# blueduino-r2.net
KiCad netlist of a schematic drawn in Altium Designer
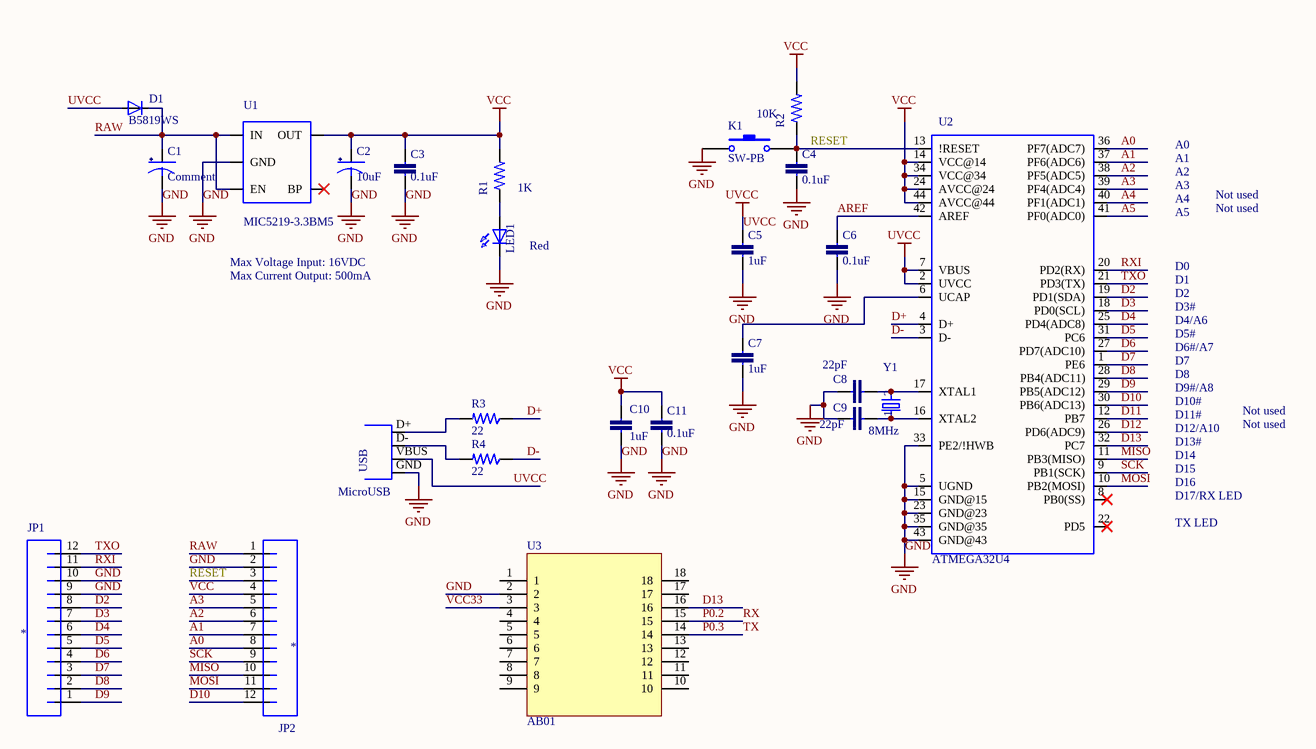
[diagram p0: blueduino-r2.SchDoc]

(export (version "E")
  (design (tool "Eeschema 10.0.6"))
  (components
    (comp (ref "C1") (value "Comment") (footprint "0603C") (libsource (lib "SparkFun") (part "CAP_POL1206")))
    (comp (ref "C2") (value "10uF") (footprint "EIA3216") (libsource (lib "SparkFun") (part "CAP_POL1206")))
    (comp (ref "C3") (value "0.1uF") (footprint "0402-CAP") (libsource (lib "SparkFun") (part "CAP0402-CAP")))
    (comp (ref "C4") (value "0.1uF") (footprint "0402-CAP") (libsource (lib "SparkFun") (part "CAP0402-CAP")))
    (comp (ref "C5") (value "1uF") (footprint "0402-CAP") (libsource (lib "SparkFun") (part "CAP0402-CAP")))
    (comp (ref "C6") (value "0.1uF") (footprint "0402-CAP") (libsource (lib "SparkFun") (part "CAP0402-CAP")))
    (comp (ref "C7") (value "1uF") (footprint "0402-CAP") (libsource (lib "SparkFun") (part "CAP0402-CAP")))
    (comp (ref "C8") (value "22pF") (footprint "0402-CAP") (libsource (lib "") (part "CAP0402-CAP_1")))
    (comp (ref "C9") (value "22pF") (footprint "0402-CAP") (libsource (lib "") (part "CAP0402-CAP_1")))
    (comp (ref "C10") (value "1uF") (footprint "0402-CAP") (libsource (lib "") (part "CAP0402-CAP_2")))
    (comp (ref "C11")
      (value "0.1uF")
      (footprint "0402-CAP")
      (libsource (lib "SparkFun") (part "CAP0402-CAP"))
    )
    (comp (ref "D1") (value "B5819WS") (footprint "SOD-323") (libsource (lib "SparkFun") (part "DIODESOD")))
    (comp (ref "JP1") (value "*") (footprint "1X12") (libsource (lib "SparkFun") (part "M12PTH")))
    (comp (ref "JP2") (value "*") (footprint "1X12") (libsource (lib "SparkFun") (part "M12PTH")))
    (comp (ref "K1")
      (value "SW-PB")
      (footprint "SPST-2")
      (description "Switch")
      (fields (field (name "PUBLISHER") "Altium Limited"))
      (libsource (lib "Miscellaneous Devices") (part "SW-PB"))
    )
    (comp (ref "LED1") (value "Red") (footprint "LED-0603") (libsource (lib "SparkFun") (part "LED0603")))
    (comp (ref "R1")
      (value "1K")
      (footprint "0402-RES")
      (libsource (lib "SparkFun") (part "RESISTOR0402-RES"))
    )
    (comp (ref "R2")
      (value "10K")
      (footprint "0402-RES")
      (libsource (lib "SparkFun") (part "RESISTOR0402-RES"))
    )
    (comp (ref "R3") (value "22") (footprint "0402-RES") (libsource (lib "") (part "RESISTOR0402-RES_1")))
    (comp (ref "R4") (value "22") (footprint "0402-RES") (libsource (lib "") (part "RESISTOR0402-RES_1")))
    (comp (ref "U1")
      (value "MIC5219-3.3BM5")
      (footprint "SOT23-5")
      (libsource (lib "SparkFun") (part "V_REG_LDOSMD"))
    )
    (comp (ref "U2")
      (value "ATMEGA32U4")
      (footprint "QFN-44-NOPAD")
      (libsource (lib "SparkFun") (part "ATMEGA32U4QFN2"))
    )
    (comp (ref "U3")
      (value "AB01")
      (footprint "CC2540-MINI")
      (description "Header, 25-Pin")
      (fields (field (name "PUBLISHER") "Altium Limited"))
      (libsource (lib "myschlib") (part "CC2541_S02"))
    )
    (comp (ref "X1")
      (value "MicroUSB")
      (footprint "USB-MICROB")
      (libsource (lib "SparkFun") (part "USB-MICROB"))
    )
    (comp (ref "Y1")
      (value "8MHz")
      (footprint "OSCCC250X320X80-4L")
      (libsource (lib "SparkFun") (part "CRYSTAL5X3"))
    )
  )
  (nets
    (net (code "1") (name "/A0") (class "Default")
      (node (ref "JP2") (pin "8") (pinfunction "8_8") (pintype "passive"))
      (node (ref "U2") (pin "36") (pinfunction "PF7(ADC7)_36") (pintype "passive"))
    )
    (net (code "2") (name "/A1") (class "Default")
      (node (ref "JP2") (pin "7") (pinfunction "7_7") (pintype "passive"))
      (node (ref "U2") (pin "37") (pinfunction "PF6(ADC6)_37") (pintype "passive"))
    )
    (net (code "3") (name "/A2") (class "Default")
      (node (ref "JP2") (pin "6") (pinfunction "6_6") (pintype "passive"))
      (node (ref "U2") (pin "38") (pinfunction "PF5(ADC5)_38") (pintype "passive"))
    )
    (net (code "4") (name "/A3") (class "Default")
      (node (ref "JP2") (pin "5") (pinfunction "5_5") (pintype "passive"))
      (node (ref "U2") (pin "39") (pinfunction "PF4(ADC4)_39") (pintype "passive"))
    )
    (net (code "5") (name "/A4") (class "Default")
      (node (ref "U2") (pin "40") (pinfunction "PF1(ADC1)_40") (pintype "passive"))
    )
    (net (code "6") (name "/A5") (class "Default")
      (node (ref "U2") (pin "41") (pinfunction "PF0(ADC0)_41") (pintype "passive"))
    )
    (net (code "7") (name "/AREF") (class "Default")
      (node (ref "C6") (pin "2") (pinfunction "2_2") (pintype "passive"))
      (node (ref "U2") (pin "42") (pinfunction "AREF_42") (pintype "passive"))
    )
    (net (code "8") (name "/D+") (class "Default")
      (node (ref "R3") (pin "1") (pinfunction "1_1") (pintype "passive"))
      (node (ref "U2") (pin "4") (pinfunction "D+_4") (pintype "passive"))
    )
    (net (code "9") (name "/D-") (class "Default")
      (node (ref "R4") (pin "1") (pinfunction "1_1") (pintype "passive"))
      (node (ref "U2") (pin "3") (pinfunction "D-_3") (pintype "passive"))
    )
    (net (code "10") (name "/D2") (class "Default")
      (node (ref "JP1") (pin "8") (pinfunction "8_8") (pintype "passive"))
      (node (ref "U2") (pin "19") (pinfunction "PD1(SDA)_19") (pintype "passive"))
    )
    (net (code "11") (name "/D3") (class "Default")
      (node (ref "JP1") (pin "7") (pinfunction "7_7") (pintype "passive"))
      (node (ref "U2") (pin "18") (pinfunction "PD0(SCL)_18") (pintype "passive"))
    )
    (net (code "12") (name "/D4") (class "Default")
      (node (ref "JP1") (pin "6") (pinfunction "6_6") (pintype "passive"))
      (node (ref "U2") (pin "25") (pinfunction "PD4(ADC8)_25") (pintype "passive"))
    )
    (net (code "13") (name "/D5") (class "Default")
      (node (ref "JP1") (pin "5") (pinfunction "5_5") (pintype "passive"))
      (node (ref "U2") (pin "31") (pinfunction "PC6_31") (pintype "passive"))
    )
    (net (code "14") (name "/D6") (class "Default")
      (node (ref "JP1") (pin "4") (pinfunction "4_4") (pintype "passive"))
      (node (ref "U2") (pin "27") (pinfunction "PD7(ADC10)_27") (pintype "passive"))
    )
    (net (code "15") (name "/D7") (class "Default")
      (node (ref "JP1") (pin "3") (pinfunction "3_3") (pintype "passive"))
      (node (ref "U2") (pin "1") (pinfunction "PE6_1") (pintype "passive"))
    )
    (net (code "16") (name "/D8") (class "Default")
      (node (ref "JP1") (pin "2") (pinfunction "2_2") (pintype "passive"))
      (node (ref "U2") (pin "28") (pinfunction "PB4(ADC11)_28") (pintype "passive"))
    )
    (net (code "17") (name "/D9") (class "Default")
      (node (ref "JP1") (pin "1") (pinfunction "1_1") (pintype "passive"))
      (node (ref "U2") (pin "29") (pinfunction "PB5(ADC12)_29") (pintype "passive"))
    )
    (net (code "18") (name "/D10") (class "Default")
      (node (ref "JP2") (pin "12") (pinfunction "12_12") (pintype "passive"))
      (node (ref "U2") (pin "30") (pinfunction "PB6(ADC13)_30") (pintype "passive"))
    )
    (net (code "19") (name "/D11") (class "Default")
      (node (ref "U2") (pin "12") (pinfunction "PB7_12") (pintype "passive"))
    )
    (net (code "20") (name "/D12") (class "Default")
      (node (ref "U2") (pin "26") (pinfunction "PD6(ADC9)_26") (pintype "passive"))
    )
    (net (code "21") (name "/D13") (class "Default")
      (node (ref "U2") (pin "32") (pinfunction "PC7_32") (pintype "passive"))
      (node (ref "U3") (pin "16") (pinfunction "16_16") (pintype "passive"))
    )
    (net (code "22") (name "/MISO") (class "Default")
      (node (ref "JP2") (pin "10") (pinfunction "10_10") (pintype "passive"))
      (node (ref "U2") (pin "11") (pinfunction "PB3(MISO)_11") (pintype "passive"))
    )
    (net (code "23") (name "/MOSI") (class "Default")
      (node (ref "JP2") (pin "11") (pinfunction "11_11") (pintype "passive"))
      (node (ref "U2") (pin "10") (pinfunction "PB2(MOSI)_10") (pintype "passive"))
    )
    (net (code "24") (name "/P0.2") (class "Default")
      (node (ref "U3") (pin "15") (pinfunction "15_15") (pintype "passive"))
    )
    (net (code "25") (name "/P0.3") (class "Default")
      (node (ref "U3") (pin "14") (pinfunction "14_14") (pintype "passive"))
    )
    (net (code "26") (name "/RAW") (class "Default")
      (node (ref "C1") (pin "A") (pinfunction "+_A") (pintype "passive"))
      (node (ref "D1") (pin "1") (pinfunction "C_1") (pintype "passive"))
      (node (ref "JP2") (pin "1") (pinfunction "1_1") (pintype "passive"))
      (node (ref "U1") (pin "1") (pinfunction "IN_1") (pintype "passive"))
      (node (ref "U1") (pin "3") (pinfunction "EN_3") (pintype "passive"))
    )
    (net (code "27") (name "/RESET") (class "Default")
      (node (ref "C4") (pin "2") (pinfunction "2_2") (pintype "passive"))
      (node (ref "JP2") (pin "3") (pinfunction "3_3") (pintype "passive"))
      (node (ref "K1") (pin "2") (pinfunction "2_2") (pintype "passive"))
      (node (ref "R2") (pin "1") (pinfunction "1_1") (pintype "passive"))
      (node (ref "U2") (pin "13") (pinfunction "!RESET_13") (pintype "passive"))
    )
    (net (code "28") (name "/RXI") (class "Default")
      (node (ref "JP1") (pin "11") (pinfunction "11_11") (pintype "passive"))
      (node (ref "U2") (pin "20") (pinfunction "PD2(RX)_20") (pintype "passive"))
    )
    (net (code "29") (name "/SCK") (class "Default")
      (node (ref "JP2") (pin "9") (pinfunction "9_9") (pintype "passive"))
      (node (ref "U2") (pin "9") (pinfunction "PB1(SCK)_9") (pintype "passive"))
    )
    (net (code "30") (name "/TXO") (class "Default")
      (node (ref "JP1") (pin "12") (pinfunction "12_12") (pintype "passive"))
      (node (ref "U2") (pin "21") (pinfunction "PD3(TX)_21") (pintype "passive"))
    )
    (net (code "31") (name "/VCC33") (class "Default")
      (node (ref "U3") (pin "3") (pinfunction "3_3") (pintype "passive"))
    )
    (net (code "32") (name "GND") (class "Default")
      (node (ref "C1") (pin "C") (pinfunction "-_C") (pintype "passive"))
      (node (ref "C10") (pin "2") (pinfunction "2_2") (pintype "passive"))
      (node (ref "C11") (pin "1") (pinfunction "1_1") (pintype "passive"))
      (node (ref "C2") (pin "C") (pinfunction "-_C") (pintype "passive"))
      (node (ref "C3") (pin "1") (pinfunction "1_1") (pintype "passive"))
      (node (ref "C4") (pin "1") (pinfunction "1_1") (pintype "passive"))
      (node (ref "C5") (pin "1") (pinfunction "1_1") (pintype "passive"))
      (node (ref "C6") (pin "1") (pinfunction "1_1") (pintype "passive"))
      (node (ref "C7") (pin "1") (pinfunction "1_1") (pintype "passive"))
      (node (ref "C8") (pin "2") (pinfunction "2_2") (pintype "passive"))
      (node (ref "C9") (pin "2") (pinfunction "2_2") (pintype "passive"))
      (node (ref "JP1") (pin "10") (pinfunction "10_10") (pintype "passive"))
      (node (ref "JP1") (pin "9") (pinfunction "9_9") (pintype "passive"))
      (node (ref "JP2") (pin "2") (pinfunction "2_2") (pintype "passive"))
      (node (ref "K1") (pin "1") (pinfunction "1_1") (pintype "passive"))
      (node (ref "LED1") (pin "C") (pinfunction "C_C") (pintype "passive"))
      (node (ref "U1") (pin "2") (pinfunction "GND_2") (pintype "passive"))
      (node (ref "U2") (pin "15") (pinfunction "GND@15_15") (pintype "passive"))
      (node (ref "U2") (pin "23") (pinfunction "GND@23_23") (pintype "passive"))
      (node (ref "U2") (pin "33") (pinfunction "PE2/!HWB_33") (pintype "passive"))
      (node (ref "U2") (pin "35") (pinfunction "GND@35_35") (pintype "passive"))
      (node (ref "U2") (pin "43") (pinfunction "GND@43_43") (pintype "passive"))
      (node (ref "U2") (pin "5") (pinfunction "UGND_5") (pintype "passive"))
      (node (ref "U3") (pin "2") (pinfunction "2_2") (pintype "passive"))
      (node (ref "X1") (pin "GND") (pinfunction "GND_GND") (pintype "passive"))
    )
    (net (code "33") (name "Net-(LED1-PadA)") (class "Default")
      (node (ref "LED1") (pin "A") (pinfunction "A_A") (pintype "passive"))
      (node (ref "R1") (pin "1") (pinfunction "1_1") (pintype "passive"))
    )
    (net (code "34") (name "Net-(R3-Pad2)") (class "Default")
      (node (ref "R3") (pin "2") (pinfunction "2_2") (pintype "passive"))
      (node (ref "X1") (pin "D+") (pinfunction "D+_D+") (pintype "passive"))
    )
    (net (code "35") (name "Net-(R4-Pad2)") (class "Default")
      (node (ref "R4") (pin "2") (pinfunction "2_2") (pintype "passive"))
      (node (ref "X1") (pin "D-") (pinfunction "D-_D-") (pintype "passive"))
    )
    (net (code "36") (name "Net-(U2-UCAP)") (class "Default")
      (node (ref "C7") (pin "2") (pinfunction "2_2") (pintype "passive"))
      (node (ref "U2") (pin "6") (pinfunction "UCAP_6") (pintype "passive"))
    )
    (net (code "37") (name "Net-(U2-XTAL1)") (class "Default")
      (node (ref "C8") (pin "1") (pinfunction "1_1") (pintype "passive"))
      (node (ref "U2") (pin "17") (pinfunction "XTAL1_17") (pintype "passive"))
      (node (ref "Y1") (pin "3") (pinfunction "2_3") (pintype "passive"))
    )
    (net (code "38") (name "Net-(U2-XTAL2)") (class "Default")
      (node (ref "C9") (pin "1") (pinfunction "1_1") (pintype "passive"))
      (node (ref "U2") (pin "16") (pinfunction "XTAL2_16") (pintype "passive"))
      (node (ref "Y1") (pin "1") (pinfunction "1_1") (pintype "passive"))
    )
    (net (code "39") (name "UVCC") (class "Default")
      (node (ref "C5") (pin "2") (pinfunction "2_2") (pintype "passive"))
      (node (ref "D1") (pin "2") (pinfunction "A_2") (pintype "passive"))
      (node (ref "U2") (pin "2") (pinfunction "UVCC_2") (pintype "passive"))
      (node (ref "U2") (pin "7") (pinfunction "VBUS_7") (pintype "passive"))
      (node (ref "X1") (pin "VBUS") (pinfunction "VBUS_VBUS") (pintype "passive"))
    )
    (net (code "40") (name "VCC") (class "Default")
      (node (ref "C10") (pin "1") (pinfunction "1_1") (pintype "passive"))
      (node (ref "C11") (pin "2") (pinfunction "2_2") (pintype "passive"))
      (node (ref "C2") (pin "A") (pinfunction "+_A") (pintype "passive"))
      (node (ref "C3") (pin "2") (pinfunction "2_2") (pintype "passive"))
      (node (ref "JP2") (pin "4") (pinfunction "4_4") (pintype "passive"))
      (node (ref "R1") (pin "2") (pinfunction "2_2") (pintype "passive"))
      (node (ref "R2") (pin "2") (pinfunction "2_2") (pintype "passive"))
      (node (ref "U1") (pin "5") (pinfunction "OUT_5") (pintype "passive"))
      (node (ref "U2") (pin "14") (pinfunction "VCC@14_14") (pintype "passive"))
      (node (ref "U2") (pin "24") (pinfunction "AVCC@24_24") (pintype "passive"))
      (node (ref "U2") (pin "34") (pinfunction "VCC@34_34") (pintype "passive"))
      (node (ref "U2") (pin "44") (pinfunction "AVCC@44_44") (pintype "passive"))
    )
    (net (code "41") (name "unconnected-(U1-BP-Pad4)") (class "Default")
      (node (ref "U1") (pin "4") (pinfunction "BP_4") (pintype "passive+no_connect"))
    )
    (net (code "42") (name "unconnected-(U2-PB0(SS)-Pad8)") (class "Default")
      (node (ref "U2") (pin "8") (pinfunction "PB0(SS)_8") (pintype "passive+no_connect"))
    )
    (net (code "43") (name "unconnected-(U2-PD5-Pad22)") (class "Default")
      (node (ref "U2") (pin "22") (pinfunction "PD5_22") (pintype "passive+no_connect"))
    )
    (net (code "44") (name "unconnected-(U3-Pad1)") (class "Default")
      (node (ref "U3") (pin "1") (pinfunction "1_1") (pintype "passive"))
    )
    (net (code "45") (name "unconnected-(U3-Pad4)") (class "Default")
      (node (ref "U3") (pin "4") (pinfunction "4_4") (pintype "passive"))
    )
    (net (code "46") (name "unconnected-(U3-Pad5)") (class "Default")
      (node (ref "U3") (pin "5") (pinfunction "5_5") (pintype "passive"))
    )
    (net (code "47") (name "unconnected-(U3-Pad6)") (class "Default")
      (node (ref "U3") (pin "6") (pinfunction "6_6") (pintype "passive"))
    )
    (net (code "48") (name "unconnected-(U3-Pad7)") (class "Default")
      (node (ref "U3") (pin "7") (pinfunction "7_7") (pintype "passive"))
    )
    (net (code "49") (name "unconnected-(U3-Pad8)") (class "Default")
      (node (ref "U3") (pin "8") (pinfunction "8_8") (pintype "passive"))
    )
    (net (code "50") (name "unconnected-(U3-Pad9)") (class "Default")
      (node (ref "U3") (pin "9") (pinfunction "9_9") (pintype "passive"))
    )
    (net (code "51") (name "unconnected-(U3-Pad10)") (class "Default")
      (node (ref "U3") (pin "10") (pinfunction "10_10") (pintype "passive"))
    )
    (net (code "52") (name "unconnected-(U3-Pad11)") (class "Default")
      (node (ref "U3") (pin "11") (pinfunction "11_11") (pintype "passive"))
    )
    (net (code "53") (name "unconnected-(U3-Pad12)") (class "Default")
      (node (ref "U3") (pin "12") (pinfunction "12_12") (pintype "passive"))
    )
    (net (code "54") (name "unconnected-(U3-Pad13)") (class "Default")
      (node (ref "U3") (pin "13") (pinfunction "13_13") (pintype "passive"))
    )
    (net (code "55") (name "unconnected-(U3-Pad17)") (class "Default")
      (node (ref "U3") (pin "17") (pinfunction "17_17") (pintype "passive"))
    )
    (net (code "56") (name "unconnected-(U3-Pad18)") (class "Default")
      (node (ref "U3") (pin "18") (pinfunction "18_18") (pintype "passive"))
    )
  )
)
